# main.net
KiCad netlist of a schematic drawn in Altium Designer
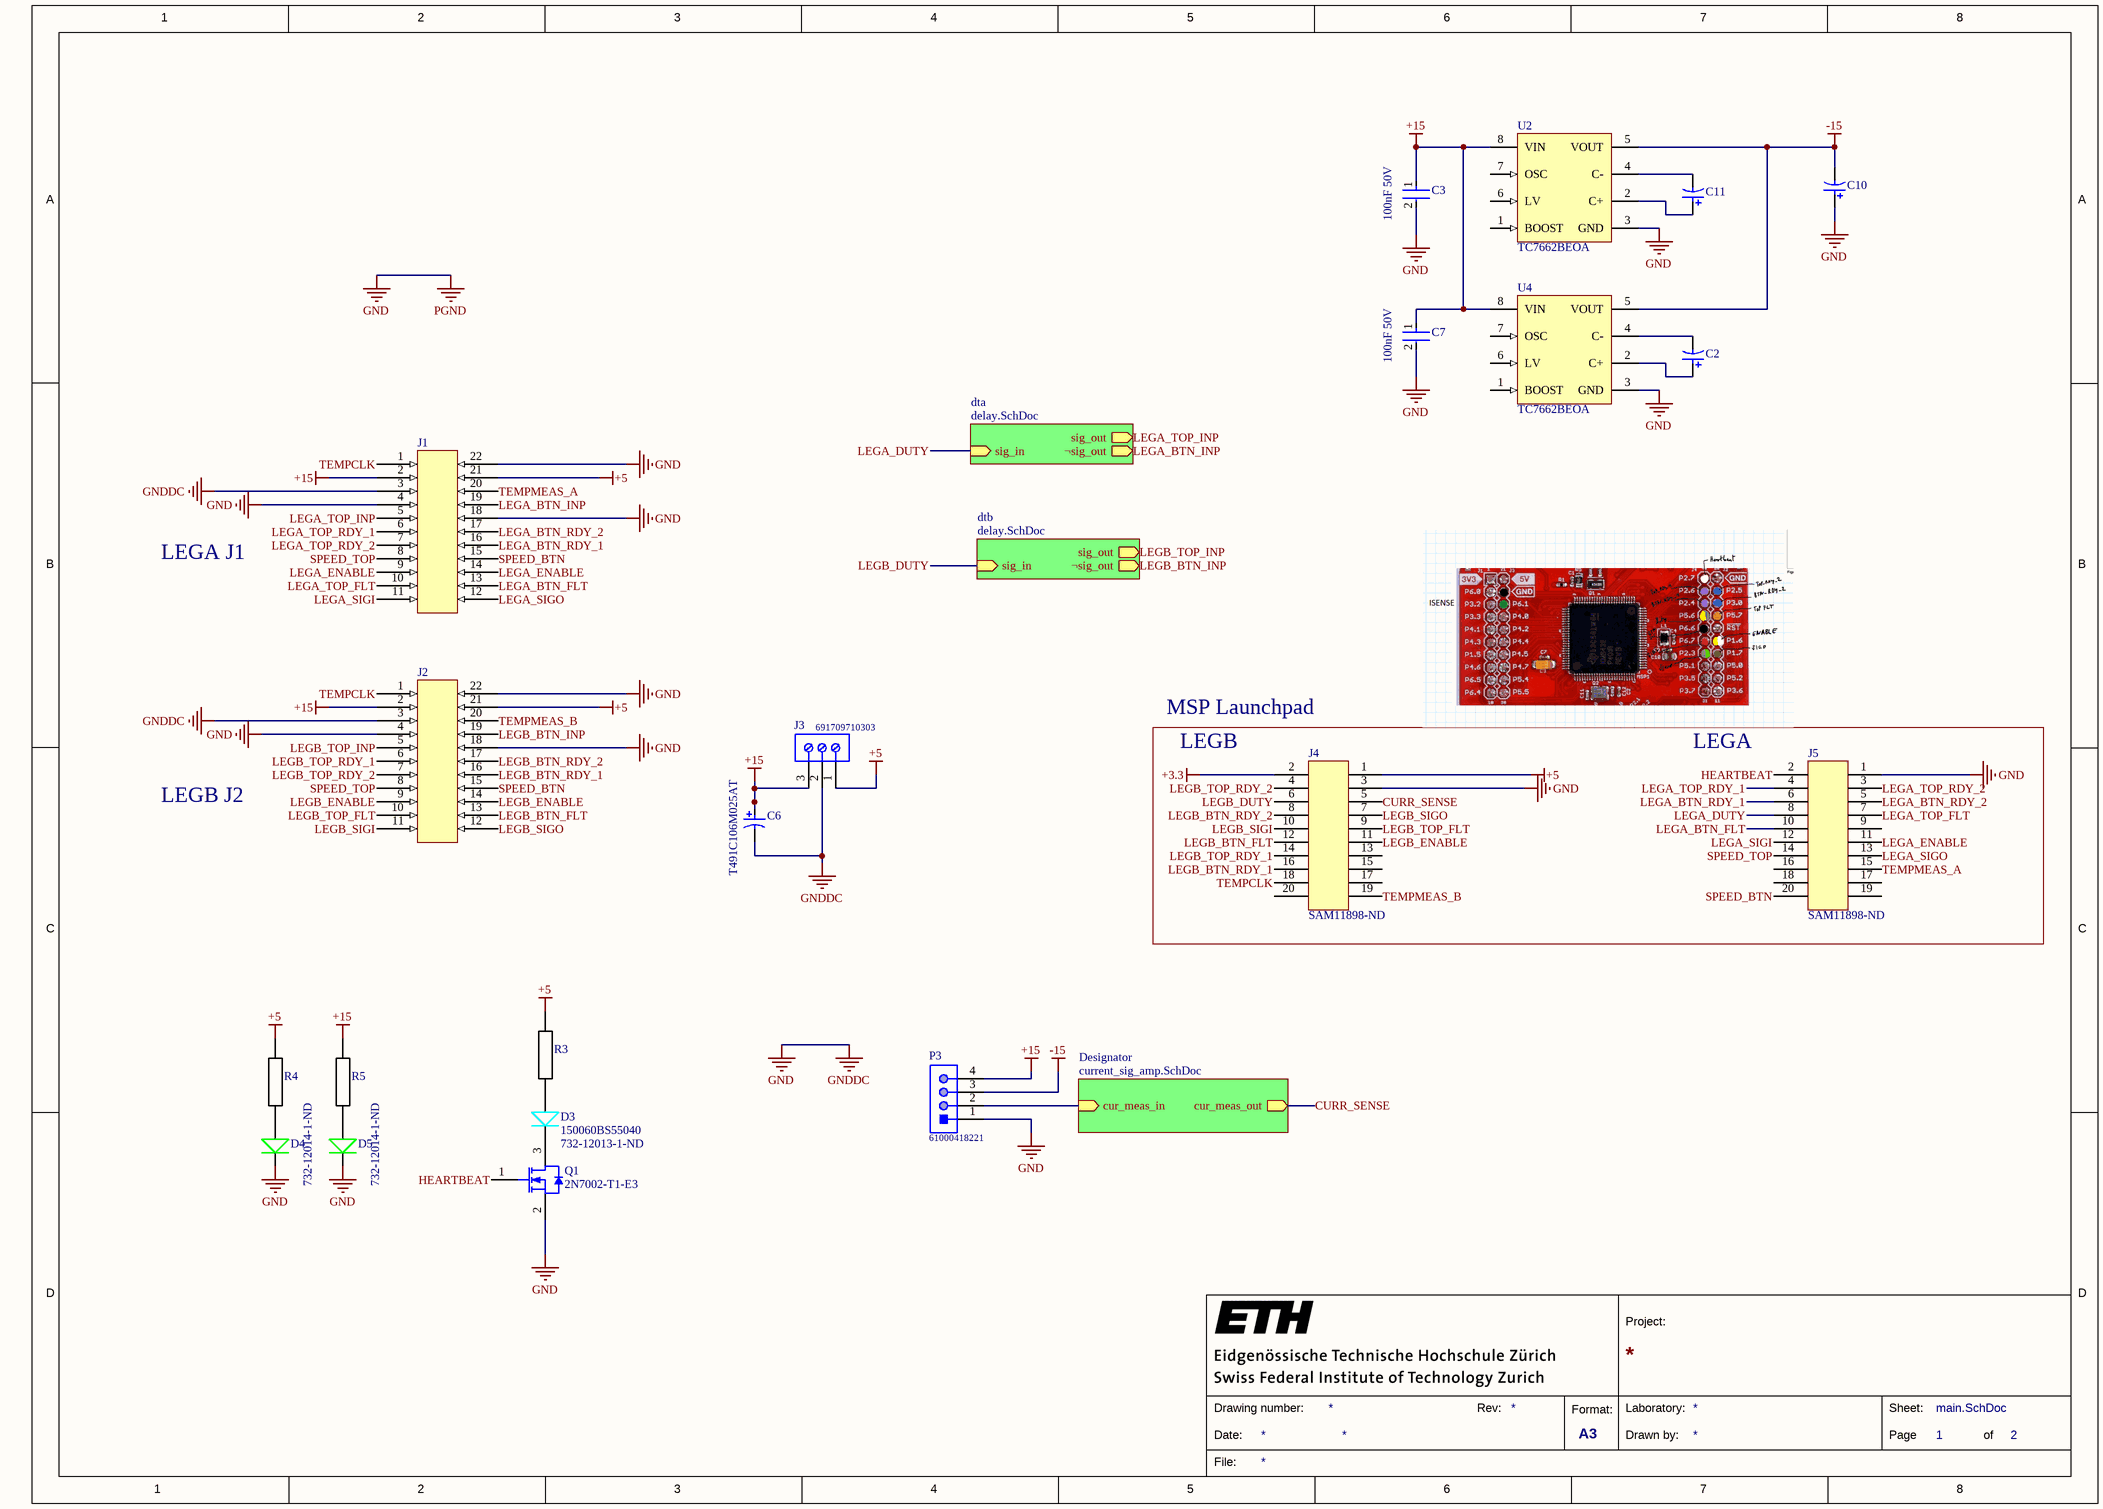
[diagram p0: main.SchDoc]

(export (version "E")
  (design (tool "Eeschema 10.0.6"))
  (components
    (comp (ref "C2")
      (value "TPSD226M025R0200")
      (footprint "AVX-7343-31_L")
      (description "Tantalum Capacitor, 22 uF, +/- 20%, 25 V, -55 to 125 degC, 2-Pin SMD, RoHS, Tape and Reel")
      (fields (field (name "TOLERANCE") "±20%") (field (name "MANUFACTURER") "AVX"))
      (libsource (lib "Altium Content Vault") (part "CAP-P-2"))
    )
    (comp (ref "C3")
      (value "100nF 50V")
      (footprint "FP-CGA3E-0_3-0_1-IPC_A")
      (description "Cap Ceramic 100nF 50V X7R 10% Pad SMD 0603 +125°C Automotive T/R")
      (fields (field (name "TOLERANCE") "10%") (field (name "VOLTAGE") "50V"))
      (libsource (lib "Altium Content Vault") (part "b4654b650e69147ec39a6b967a45e02"))
    )
    (comp (ref "C6")
      (value "T491C106M025AT")
      (footprint "KEMT-T491-C_L")
      (fields (field (name "MANUFACTURER") "Kemet") (field (name "VOLTAGE") "25VDC"))
      (libsource (lib "Altium Content Vault") (part "CAP-P-2"))
    )
    (comp (ref "C7")
      (value "100nF 50V")
      (footprint "FP-CGA3E-0_3-0_1-IPC_A")
      (description "Cap Ceramic 100nF 50V X7R 10% Pad SMD 0603 +125°C Automotive T/R")
      (fields (field (name "TOLERANCE") "10%") (field (name "VOLTAGE") "50V"))
      (libsource (lib "Altium Content Vault") (part "b4654b650e69147ec39a6b967a45e02"))
    )
    (comp (ref "C10")
      (value "TPSD226M025R0200")
      (footprint "AVX-7343-31_L")
      (description "Tantalum Capacitor, 22 uF, +/- 20%, 25 V, -55 to 125 degC, 2-Pin SMD, RoHS, Tape and Reel")
      (fields (field (name "TOLERANCE") "±20%") (field (name "MANUFACTURER") "AVX"))
      (libsource (lib "Altium Content Vault") (part "CAP-P-2"))
    )
    (comp (ref "C11")
      (value "TPSD226M025R0200")
      (footprint "AVX-7343-31_L")
      (description "Tantalum Capacitor, 22 uF, +/- 20%, 25 V, -55 to 125 degC, 2-Pin SMD, RoHS, Tape and Reel")
      (fields (field (name "TOLERANCE") "±20%") (field (name "MANUFACTURER") "AVX"))
      (libsource (lib "Altium Content Vault") (part "CAP-P-2"))
    )
    (comp (ref "D3")
      (value "150060BS55040")
      (footprint "LED_BLUE_0603")
      (fields (field (name "SUPPLIER PART NUMBER 1") "732-12013-1-ND"))
      (libsource (lib "coil_driver_lib") (part "led_blue_0603"))
    )
    (comp (ref "D4")
      (value "732-12014-1-ND")
      (footprint "LED_GREEN_0603")
      (fields (field (name "SUPPLIER PART NUMBER 1") "732-12014-1-ND"))
      (libsource (lib "coil_driver_lib") (part "led_green_0603"))
    )
    (comp (ref "D5")
      (value "732-12014-1-ND")
      (footprint "LED_GREEN_0603")
      (fields (field (name "SUPPLIER PART NUMBER 1") "732-12014-1-ND"))
      (libsource (lib "coil_driver_lib") (part "led_green_0603"))
    )
    (comp (ref "J1")
      (value "header_22_milligrid")
      (footprint "header_22_milligrid")
      (libsource (lib "coil_driver_lib") (part "header_22_milligrid"))
    )
    (comp (ref "J2")
      (value "header_22_milligrid")
      (footprint "header_22_milligrid")
      (libsource (lib "coil_driver_lib") (part "header_22_milligrid"))
    )
    (comp (ref "J3")
      (value "691709710303")
      (footprint "691709710303")
      (description "Serie 7097 - 5.00 mm Horizontal Entry SMT with Pressure Clamp WR-TBL, 3 pin")
      (fields (field (name "MANUFACTURER") "Wurth Elektronik") (field (name "PUBLISHER") "WurthElektronik"))
      (libsource (lib "Altium Content Vault") (part "WE-CN-1P-F-TB3"))
    )
    (comp (ref "J4")
      (value "header_f_20_imp")
      (footprint "header_f_20_imp")
      (fields (field (name "SUPPLIER PART NUMBER 1") "SAM11898-ND"))
      (libsource (lib "coil_driver_lib") (part "header_f_20_imp"))
    )
    (comp (ref "J5")
      (value "header_f_20_imp")
      (footprint "header_f_20_imp")
      (fields (field (name "SUPPLIER PART NUMBER 1") "SAM11898-ND"))
      (libsource (lib "coil_driver_lib") (part "header_f_20_imp"))
    )
    (comp (ref "P3")
      (value "61000418221")
      (footprint "61000418221")
      (description "SMT Vertical Pin Header WR-PHD, Pitch 2.54 mm, Single Row, 4 pins")
      (fields (field (name "MANUFACTURER") "Wurth Elektronik") (field (name "PUBLISHER") "WurthElektronik"))
      (libsource (lib "Altium Content Vault") (part "WE-CN-1P-M-R4"))
    )
    (comp (ref "Q1")
      (value "2N7002-T1-E3")
      (footprint "VISH-TO-236-3_A_L")
      (description "N-Channel MOSFET, 115 mA, 60 V, -55 to 150 degC, 3-Pin SOT23, RoHS, Tape and Reel")
      (fields (field (name "MANUFACTURER") "Vishay"))
      (libsource (lib "Altium Content Vault") (part "NEMOS-GSD-3"))
    )
    (comp (ref "R3")
      (value "res_smd")
      (footprint "0805")
      (libsource (lib "coil_driver_lib") (part "res_smd"))
    )
    (comp (ref "R4")
      (value "res_smd")
      (footprint "0805")
      (libsource (lib "coil_driver_lib") (part "res_smd"))
    )
    (comp (ref "R5")
      (value "res_smd")
      (footprint "0805")
      (libsource (lib "coil_driver_lib") (part "res_smd"))
    )
    (comp (ref "U2")
      (value "TC7662BEOA")
      (footprint "SOIC-OA8_M")
      (description "Charge Pump DC-to-DC Voltage Converter, 10kHz, 35kHz, 8-Pin SOIC 150mil, Industrial Temperature")
      (libsource (lib "Altium Content Vault") (part "PM-CHP-TC1044-IL8"))
    )
    (comp (ref "U4")
      (value "TC7662BEOA")
      (footprint "SOIC-OA8_M")
      (description "Charge Pump DC-to-DC Voltage Converter, 10kHz, 35kHz, 8-Pin SOIC 150mil, Industrial Temperature")
      (libsource (lib "Altium Content Vault") (part "PM-CHP-TC1044-IL8"))
    )
  )
  (nets
    (net (code "1") (name "+3.3") (class "Default") (node (ref "J4") (pin "2") (pintype "passive")))
    (net (code "2") (name "+5") (class "Default")
      (node (ref "J1") (pin "21") (pintype "input"))
      (node (ref "J2") (pin "21") (pintype "input"))
      (node (ref "J3") (pin "1") (pinfunction "1_1") (pintype "passive"))
      (node (ref "J4") (pin "1") (pintype "passive"))
      (node (ref "R3") (pin "1") (pinfunction "1_1") (pintype "passive"))
      (node (ref "R4") (pin "1") (pinfunction "1_1") (pintype "passive"))
    )
    (net (code "3") (name "+15") (class "Default")
      (node (ref "C3") (pin "1") (pinfunction "1_1") (pintype "passive"))
      (node (ref "C6") (pin "1") (pinfunction "1_1") (pintype "passive"))
      (node (ref "C7") (pin "1") (pinfunction "1_1") (pintype "passive"))
      (node (ref "J1") (pin "2") (pintype "input"))
      (node (ref "J2") (pin "2") (pintype "input"))
      (node (ref "J3") (pin "3") (pinfunction "3_3") (pintype "passive"))
      (node (ref "P3") (pin "4") (pinfunction "4_4") (pintype "passive"))
      (node (ref "R5") (pin "1") (pinfunction "1_1") (pintype "passive"))
      (node (ref "U2") (pin "8") (pinfunction "VIN_8") (pintype "power_in"))
      (node (ref "U4") (pin "8") (pinfunction "VIN_8") (pintype "power_in"))
    )
    (net (code "4") (name "-15") (class "Default")
      (node (ref "C10") (pin "2") (pinfunction "2_2") (pintype "passive"))
      (node (ref "P3") (pin "3") (pinfunction "3_3") (pintype "passive"))
      (node (ref "U2") (pin "5") (pinfunction "VOUT_5") (pintype "power_in"))
      (node (ref "U4") (pin "5") (pinfunction "VOUT_5") (pintype "power_in"))
    )
    (net (code "5") (name "/CURR_SENSE") (class "Default") (node (ref "J4") (pin "5") (pintype "passive")))
    (net (code "6") (name "/HEARTBEAT") (class "Default")
      (node (ref "J5") (pin "2") (pintype "passive"))
      (node (ref "Q1") (pin "1") (pinfunction "G_1") (pintype "passive"))
    )
    (net (code "7") (name "/LEGA_BTN_FLT") (class "Default")
      (node (ref "J1") (pin "13") (pintype "input"))
      (node (ref "J5") (pin "10") (pintype "passive"))
    )
    (net (code "8") (name "/LEGA_BTN_INP") (class "Default") (node (ref "J1") (pin "19") (pintype "input")))
    (net (code "9") (name "/LEGA_BTN_RDY_1") (class "Default")
      (node (ref "J1") (pin "16") (pintype "input"))
      (node (ref "J5") (pin "6") (pintype "passive"))
    )
    (net (code "10") (name "/LEGA_BTN_RDY_2") (class "Default")
      (node (ref "J1") (pin "17") (pintype "input"))
      (node (ref "J5") (pin "5") (pintype "passive"))
    )
    (net (code "11") (name "/LEGA_DUTY") (class "Default") (node (ref "J5") (pin "8") (pintype "passive")))
    (net (code "12") (name "/LEGA_ENABLE") (class "Default")
      (node (ref "J1") (pin "14") (pintype "input"))
      (node (ref "J1") (pin "9") (pintype "input"))
      (node (ref "J5") (pin "11") (pintype "passive"))
    )
    (net (code "13") (name "/LEGA_SIGI") (class "Default")
      (node (ref "J1") (pin "11") (pintype "input"))
      (node (ref "J5") (pin "12") (pintype "passive"))
    )
    (net (code "14") (name "/LEGA_SIGO") (class "Default")
      (node (ref "J1") (pin "12") (pintype "input"))
      (node (ref "J5") (pin "13") (pintype "passive"))
    )
    (net (code "15") (name "/LEGA_TOP_FLT") (class "Default")
      (node (ref "J1") (pin "10") (pintype "input"))
      (node (ref "J5") (pin "7") (pintype "passive"))
    )
    (net (code "16") (name "/LEGA_TOP_INP") (class "Default") (node (ref "J1") (pin "5") (pintype "input")))
    (net (code "17") (name "/LEGA_TOP_RDY_1") (class "Default")
      (node (ref "J1") (pin "6") (pintype "input"))
      (node (ref "J5") (pin "4") (pintype "passive"))
    )
    (net (code "18") (name "/LEGA_TOP_RDY_2") (class "Default")
      (node (ref "J1") (pin "7") (pintype "input"))
      (node (ref "J5") (pin "3") (pintype "passive"))
    )
    (net (code "19") (name "/LEGB_BTN_FLT") (class "Default")
      (node (ref "J2") (pin "13") (pintype "input"))
      (node (ref "J4") (pin "12") (pintype "passive"))
    )
    (net (code "20") (name "/LEGB_BTN_INP") (class "Default") (node (ref "J2") (pin "19") (pintype "input")))
    (net (code "21") (name "/LEGB_BTN_RDY_1") (class "Default")
      (node (ref "J2") (pin "16") (pintype "input"))
      (node (ref "J4") (pin "16") (pintype "passive"))
    )
    (net (code "22") (name "/LEGB_BTN_RDY_2") (class "Default")
      (node (ref "J2") (pin "17") (pintype "input"))
      (node (ref "J4") (pin "8") (pintype "passive"))
    )
    (net (code "23") (name "/LEGB_DUTY") (class "Default") (node (ref "J4") (pin "6") (pintype "passive")))
    (net (code "24") (name "/LEGB_ENABLE") (class "Default")
      (node (ref "J2") (pin "14") (pintype "input"))
      (node (ref "J2") (pin "9") (pintype "input"))
      (node (ref "J4") (pin "11") (pintype "passive"))
    )
    (net (code "25") (name "/LEGB_SIGI") (class "Default")
      (node (ref "J2") (pin "11") (pintype "input"))
      (node (ref "J4") (pin "10") (pintype "passive"))
    )
    (net (code "26") (name "/LEGB_SIGO") (class "Default")
      (node (ref "J2") (pin "12") (pintype "input"))
      (node (ref "J4") (pin "7") (pintype "passive"))
    )
    (net (code "27") (name "/LEGB_TOP_FLT") (class "Default")
      (node (ref "J2") (pin "10") (pintype "input"))
      (node (ref "J4") (pin "9") (pintype "passive"))
    )
    (net (code "28") (name "/LEGB_TOP_INP") (class "Default") (node (ref "J2") (pin "5") (pintype "input")))
    (net (code "29") (name "/LEGB_TOP_RDY_1") (class "Default")
      (node (ref "J2") (pin "6") (pintype "input"))
      (node (ref "J4") (pin "14") (pintype "passive"))
    )
    (net (code "30") (name "/LEGB_TOP_RDY_2") (class "Default")
      (node (ref "J2") (pin "7") (pintype "input"))
      (node (ref "J4") (pin "4") (pintype "passive"))
    )
    (net (code "31") (name "/SPEED_BTN") (class "Default")
      (node (ref "J1") (pin "15") (pintype "input"))
      (node (ref "J2") (pin "15") (pintype "input"))
      (node (ref "J5") (pin "20") (pintype "passive"))
    )
    (net (code "32") (name "/SPEED_TOP") (class "Default")
      (node (ref "J1") (pin "8") (pintype "input"))
      (node (ref "J2") (pin "8") (pintype "input"))
      (node (ref "J5") (pin "14") (pintype "passive"))
    )
    (net (code "33") (name "/TEMPCLK") (class "Default")
      (node (ref "J1") (pin "1") (pintype "input"))
      (node (ref "J2") (pin "1") (pintype "input"))
      (node (ref "J4") (pin "18") (pintype "passive"))
    )
    (net (code "34") (name "/TEMPMEAS_A") (class "Default")
      (node (ref "J1") (pin "20") (pintype "input"))
      (node (ref "J5") (pin "15") (pintype "passive"))
    )
    (net (code "35") (name "/TEMPMEAS_B") (class "Default")
      (node (ref "J2") (pin "20") (pintype "input"))
      (node (ref "J4") (pin "19") (pintype "passive"))
    )
    (net (code "36") (name "/cur_meas_in") (class "Default")
      (node (ref "P3") (pin "2") (pinfunction "2_2") (pintype "passive"))
    )
    (net (code "37") (name "GND") (class "Default")
      (node (ref "C10") (pin "1") (pinfunction "1_1") (pintype "passive"))
      (node (ref "C3") (pin "2") (pinfunction "2_2") (pintype "passive"))
      (node (ref "C6") (pin "2") (pinfunction "2_2") (pintype "passive"))
      (node (ref "C7") (pin "2") (pinfunction "2_2") (pintype "passive"))
      (node (ref "D4") (pin "C") (pinfunction "C_C") (pintype "passive"))
      (node (ref "D5") (pin "C") (pinfunction "C_C") (pintype "passive"))
      (node (ref "J1") (pin "18") (pintype "input"))
      (node (ref "J1") (pin "22") (pintype "input"))
      (node (ref "J1") (pin "3") (pintype "input"))
      (node (ref "J1") (pin "4") (pintype "input"))
      (node (ref "J2") (pin "18") (pintype "input"))
      (node (ref "J2") (pin "22") (pintype "input"))
      (node (ref "J2") (pin "3") (pintype "input"))
      (node (ref "J2") (pin "4") (pintype "input"))
      (node (ref "J3") (pin "2") (pinfunction "2_2") (pintype "passive"))
      (node (ref "J4") (pin "3") (pintype "passive"))
      (node (ref "J5") (pin "1") (pintype "passive"))
      (node (ref "P3") (pin "1") (pinfunction "1_1") (pintype "passive"))
      (node (ref "Q1") (pin "2") (pinfunction "S_2") (pintype "passive"))
      (node (ref "U2") (pin "3") (pinfunction "GND_3") (pintype "power_in"))
      (node (ref "U4") (pin "3") (pinfunction "GND_3") (pintype "power_in"))
    )
    (net (code "38") (name "Net-(D3-PadA)") (class "Default")
      (node (ref "D3") (pin "A") (pinfunction "A_A") (pintype "passive"))
      (node (ref "R3") (pin "2") (pinfunction "2_2") (pintype "passive"))
    )
    (net (code "39") (name "Net-(D4-PadA)") (class "Default")
      (node (ref "D4") (pin "A") (pinfunction "A_A") (pintype "passive"))
      (node (ref "R4") (pin "2") (pinfunction "2_2") (pintype "passive"))
    )
    (net (code "40") (name "Net-(D5-PadA)") (class "Default")
      (node (ref "D5") (pin "A") (pinfunction "A_A") (pintype "passive"))
      (node (ref "R5") (pin "2") (pinfunction "2_2") (pintype "passive"))
    )
    (net (code "41") (name "Net-(Q1-D)") (class "Default")
      (node (ref "D3") (pin "C") (pinfunction "C_C") (pintype "passive"))
      (node (ref "Q1") (pin "3") (pinfunction "D_3") (pintype "passive"))
    )
    (net (code "42") (name "Net-(U2-C+)") (class "Default")
      (node (ref "C11") (pin "1") (pinfunction "1_1") (pintype "passive"))
      (node (ref "U2") (pin "2") (pinfunction "C+_2") (pintype "passive"))
    )
    (net (code "43") (name "Net-(U2-C-)") (class "Default")
      (node (ref "C11") (pin "2") (pinfunction "2_2") (pintype "passive"))
      (node (ref "U2") (pin "4") (pinfunction "C-_4") (pintype "passive"))
    )
    (net (code "44") (name "Net-(U4-C+)") (class "Default")
      (node (ref "C2") (pin "1") (pinfunction "1_1") (pintype "passive"))
      (node (ref "U4") (pin "2") (pinfunction "C+_2") (pintype "passive"))
    )
    (net (code "45") (name "Net-(U4-C-)") (class "Default")
      (node (ref "C2") (pin "2") (pinfunction "2_2") (pintype "passive"))
      (node (ref "U4") (pin "4") (pinfunction "C-_4") (pintype "passive"))
    )
    (net (code "46") (name "unconnected-(J4-Pad13)") (class "Default")
      (node (ref "J4") (pin "13") (pintype "passive"))
    )
    (net (code "47") (name "unconnected-(J4-Pad15)") (class "Default")
      (node (ref "J4") (pin "15") (pintype "passive"))
    )
    (net (code "48") (name "unconnected-(J4-Pad17)") (class "Default")
      (node (ref "J4") (pin "17") (pintype "passive"))
    )
    (net (code "49") (name "unconnected-(J4-Pad20)") (class "Default")
      (node (ref "J4") (pin "20") (pintype "passive"))
    )
    (net (code "50") (name "unconnected-(J5-Pad9)") (class "Default")
      (node (ref "J5") (pin "9") (pintype "passive"))
    )
    (net (code "51") (name "unconnected-(J5-Pad16)") (class "Default")
      (node (ref "J5") (pin "16") (pintype "passive"))
    )
    (net (code "52") (name "unconnected-(J5-Pad17)") (class "Default")
      (node (ref "J5") (pin "17") (pintype "passive"))
    )
    (net (code "53") (name "unconnected-(J5-Pad18)") (class "Default")
      (node (ref "J5") (pin "18") (pintype "passive"))
    )
    (net (code "54") (name "unconnected-(J5-Pad19)") (class "Default")
      (node (ref "J5") (pin "19") (pintype "passive"))
    )
    (net (code "55") (name "unconnected-(U2-BOOST-Pad1)") (class "Default")
      (node (ref "U2") (pin "1") (pinfunction "BOOST_1") (pintype "input"))
    )
    (net (code "56") (name "unconnected-(U2-LV-Pad6)") (class "Default")
      (node (ref "U2") (pin "6") (pinfunction "LV_6") (pintype "input"))
    )
    (net (code "57") (name "unconnected-(U2-OSC-Pad7)") (class "Default")
      (node (ref "U2") (pin "7") (pinfunction "OSC_7") (pintype "input"))
    )
    (net (code "58") (name "unconnected-(U4-BOOST-Pad1)") (class "Default")
      (node (ref "U4") (pin "1") (pinfunction "BOOST_1") (pintype "input"))
    )
    (net (code "59") (name "unconnected-(U4-LV-Pad6)") (class "Default")
      (node (ref "U4") (pin "6") (pinfunction "LV_6") (pintype "input"))
    )
    (net (code "60") (name "unconnected-(U4-OSC-Pad7)") (class "Default")
      (node (ref "U4") (pin "7") (pinfunction "OSC_7") (pintype "input"))
    )
  )
)
